# MAIN_BOARD_POWER.net
KiCad netlist of a schematic drawn in Altium Designer
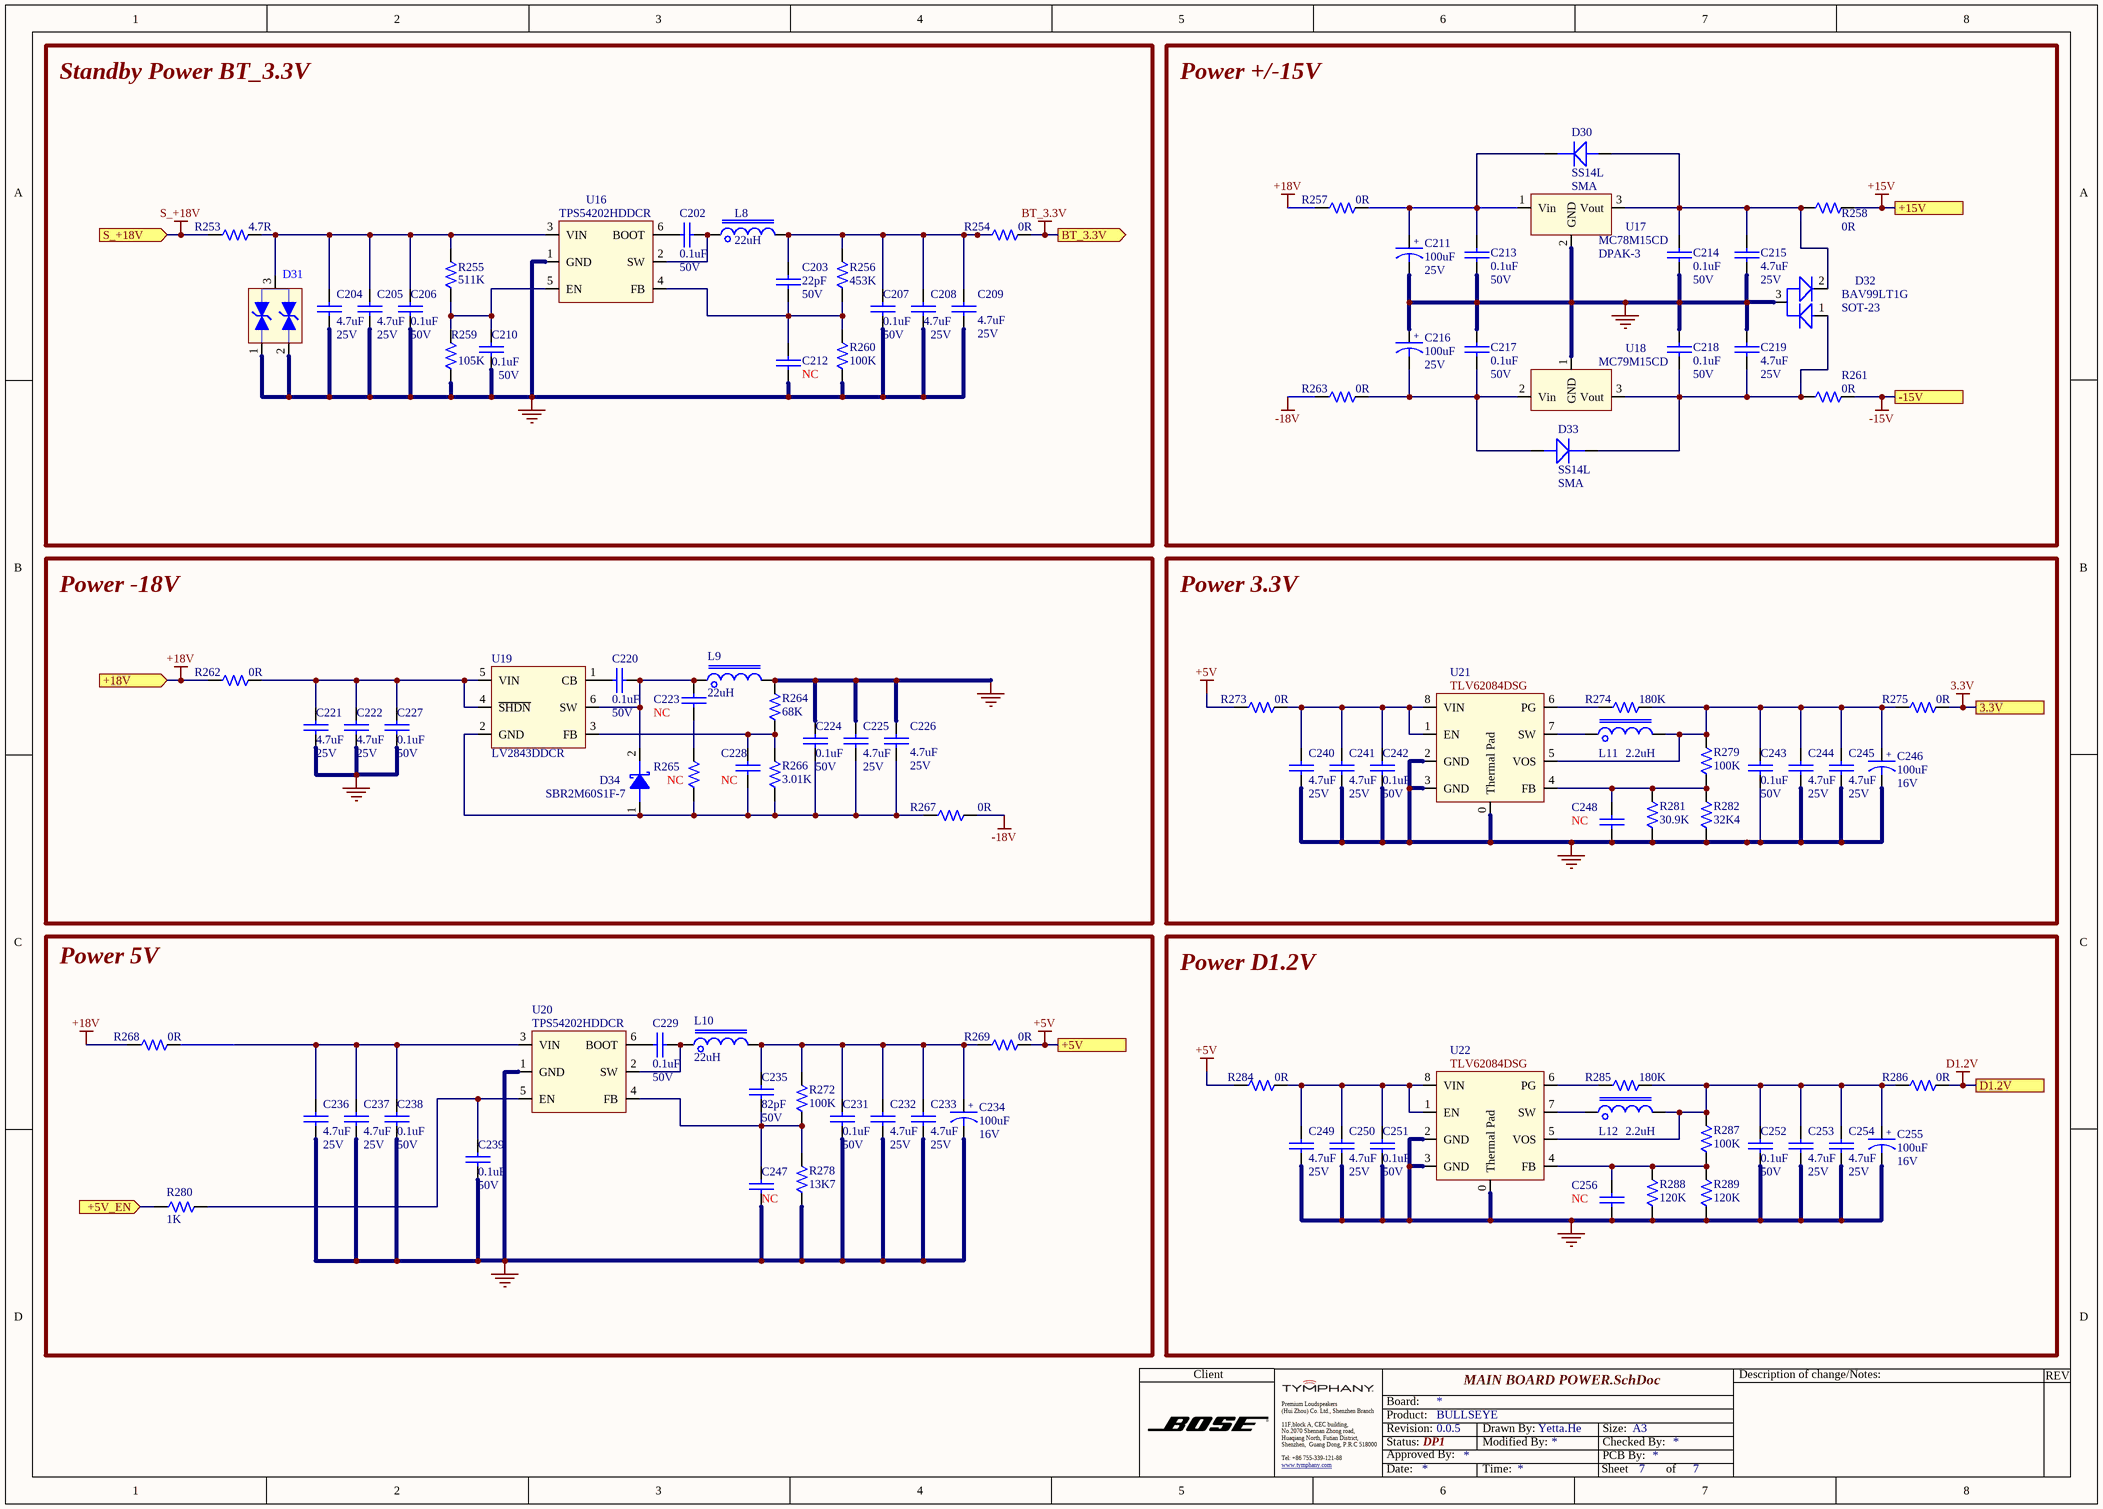
[diagram p0: MAIN BOARD POWER.SchDoc]

(export (version "E")
  (design (tool "Eeschema 10.0.6"))
  (components
    (comp (ref "C202")
      (value "0.1uF")
      (footprint "CAPC0402-RW")
      (description "CAP X7R .10UF 50V +-10% 0402 WALSIN L")
      (fields
        (field (name "TOLERANCE") "10%")
        (field (name "VOLTAGE") "50V")
        (field (name "Comment") "PWL456470-1040")
      )
      (libsource (lib "P-Capacitors") (part "CAP0402 0.1uF 50V 10%"))
    )
    (comp (ref "C203")
      (value "22pF")
      (footprint "CAPC0402-RW")
      (description "CHIP CAP 5% 50V 0402 NPO 22pF")
      (fields
        (field (name "TOLERANCE") "5%")
        (field (name "VOLTAGE") "50V")
        (field (name "Comment") "PWL410370-2200")
      )
      (libsource (lib "P-Capacitors") (part "CAP0402 22pF 50V 5%"))
    )
    (comp (ref "C204")
      (value "4.7uF")
      (footprint "CAPC0603-RW")
      (description "CAP X7R 4.7UF 25V +-10% 0603 WALSIN L")
      (fields (field (name "MFG") "WALSIN") (field (name "TOLERANCE") "10%") (field (name "VOLTAGE") "25V"))
      (libsource (lib "P-Capacitors") (part "CAP0603 4.7uF 25V 10%_X7R_WALSIN"))
    )
    (comp (ref "C205")
      (value "4.7uF")
      (footprint "CAPC0603-RW")
      (description "CAP X7R 4.7UF 25V +-10% 0603 WALSIN L")
      (fields (field (name "MFG") "WALSIN") (field (name "TOLERANCE") "10%") (field (name "VOLTAGE") "25V"))
      (libsource (lib "P-Capacitors") (part "CAP0603 4.7uF 25V 10%_X7R_WALSIN"))
    )
    (comp (ref "C206")
      (value "0.1uF")
      (footprint "CAPC0402-RW")
      (description "CAP X7R .10UF 50V +-10% 0402 WALSIN L")
      (fields
        (field (name "TOLERANCE") "10%")
        (field (name "VOLTAGE") "50V")
        (field (name "Comment") "PWL456470-1040")
      )
      (libsource (lib "P-Capacitors") (part "CAP0402 0.1uF 50V 10%"))
    )
    (comp (ref "C207")
      (value "0.1uF")
      (footprint "CAPC0402-RW")
      (description "CAP X7R .10UF 50V +-10% 0402 WALSIN L")
      (fields
        (field (name "TOLERANCE") "10%")
        (field (name "VOLTAGE") "50V")
        (field (name "Comment") "PWL456470-1040")
      )
      (libsource (lib "P-Capacitors") (part "CAP0402 0.1uF 50V 10%"))
    )
    (comp (ref "C208")
      (value "4.7uF")
      (footprint "CAPC0603-RW")
      (description "CAP X7R 4.7UF 25V +-10% 0603 WALSIN L")
      (fields (field (name "MFG") "WALSIN") (field (name "TOLERANCE") "10%") (field (name "VOLTAGE") "25V"))
      (libsource (lib "P-Capacitors") (part "CAP0603 4.7uF 25V 10%_X7R_WALSIN"))
    )
    (comp (ref "C209")
      (value "4.7uF")
      (footprint "CAPC0603-RW")
      (description "CAP X7R 4.7UF 25V +-10% 0603 WALSIN L")
      (fields (field (name "MFG") "WALSIN") (field (name "TOLERANCE") "10%") (field (name "VOLTAGE") "25V"))
      (libsource (lib "P-Capacitors") (part "CAP0603 4.7uF 25V 10%_X7R_WALSIN"))
    )
    (comp (ref "C210")
      (value "0.1uF")
      (footprint "CAPC0402-RW")
      (description "CAP X7R .10UF 50V +-10% 0402 WALSIN L")
      (fields
        (field (name "TOLERANCE") "10%")
        (field (name "VOLTAGE") "50V")
        (field (name "Comment") "PWL456470-1040")
      )
      (libsource (lib "P-Capacitors") (part "CAP0402 0.1uF 50V 10%"))
    )
    (comp (ref "C211")
      (value "100uF")
      (footprint "CASE - D8")
      (description "E 100UF 25V +-20% 6.3X7. VEJ101M1E K")
      (fields
        (field (name "MFG") "LELON")
        (field (name "MFG PART") "VEJ101M1ETR-0607")
        (field (name "VOLTAGE") "25V")
      )
      (libsource (lib "P-Capacitors") (part "CAP E 100uF 25V 20% SMD_VEJ101M1ETR-0607"))
    )
    (comp (ref "C212")
      (value "NC")
      (footprint "CAPC0603-RW")
      (fields (field (name "Comment") "CAP0603 NC"))
      (libsource (lib "Temporary") (part "CAP0603 NC"))
    )
    (comp (ref "C213")
      (value "0.1uF")
      (footprint "CAPC0402-RW")
      (description "CAP X7R .10UF 50V +-10% 0402 WALSIN L")
      (fields
        (field (name "TOLERANCE") "10%")
        (field (name "VOLTAGE") "50V")
        (field (name "Comment") "PWL456470-1040")
      )
      (libsource (lib "P-Capacitors") (part "CAP0402 0.1uF 50V 10%"))
    )
    (comp (ref "C214")
      (value "0.1uF")
      (footprint "CAPC0402-RW")
      (description "CAP X7R .10UF 50V +-10% 0402 WALSIN L")
      (fields
        (field (name "TOLERANCE") "10%")
        (field (name "VOLTAGE") "50V")
        (field (name "Comment") "PWL456470-1040")
      )
      (libsource (lib "P-Capacitors") (part "CAP0402 0.1uF 50V 10%"))
    )
    (comp (ref "C215")
      (value "4.7uF")
      (footprint "CAPC0603-RW")
      (description "CAP X7R 4.7UF 25V +-10% 0603 WALSIN L")
      (fields (field (name "MFG") "WALSIN") (field (name "TOLERANCE") "10%") (field (name "VOLTAGE") "25V"))
      (libsource (lib "P-Capacitors") (part "CAP0603 4.7uF 25V 10%_X7R_WALSIN"))
    )
    (comp (ref "C216")
      (value "100uF")
      (footprint "CASE - D8")
      (description "E 100UF 25V +-20% 6.3X7. VEJ101M1E K")
      (fields
        (field (name "MFG") "LELON")
        (field (name "MFG PART") "VEJ101M1ETR-0607")
        (field (name "VOLTAGE") "25V")
      )
      (libsource (lib "P-Capacitors") (part "CAP E 100uF 25V 20% SMD_VEJ101M1ETR-0607"))
    )
    (comp (ref "C217")
      (value "0.1uF")
      (footprint "CAPC0402-RW")
      (description "CAP X7R .10UF 50V +-10% 0402 WALSIN L")
      (fields
        (field (name "TOLERANCE") "10%")
        (field (name "VOLTAGE") "50V")
        (field (name "Comment") "PWL456470-1040")
      )
      (libsource (lib "P-Capacitors") (part "CAP0402 0.1uF 50V 10%"))
    )
    (comp (ref "C218")
      (value "0.1uF")
      (footprint "CAPC0402-RW")
      (description "CAP X7R .10UF 50V +-10% 0402 WALSIN L")
      (fields
        (field (name "TOLERANCE") "10%")
        (field (name "VOLTAGE") "50V")
        (field (name "Comment") "PWL456470-1040")
      )
      (libsource (lib "P-Capacitors") (part "CAP0402 0.1uF 50V 10%"))
    )
    (comp (ref "C219")
      (value "4.7uF")
      (footprint "CAPC0603-RW")
      (description "CAP X7R 4.7UF 25V +-10% 0603 WALSIN L")
      (fields (field (name "MFG") "WALSIN") (field (name "TOLERANCE") "10%") (field (name "VOLTAGE") "25V"))
      (libsource (lib "P-Capacitors") (part "CAP0603 4.7uF 25V 10%_X7R_WALSIN"))
    )
    (comp (ref "C220")
      (value "0.1uF")
      (footprint "CAPC0402-RW")
      (description "CAP X7R .10UF 50V +-10% 0402 WALSIN L")
      (fields
        (field (name "TOLERANCE") "10%")
        (field (name "VOLTAGE") "50V")
        (field (name "Comment") "PWL456470-1040")
      )
      (libsource (lib "P-Capacitors") (part "CAP0402 0.1uF 50V 10%"))
    )
    (comp (ref "C221")
      (value "4.7uF")
      (footprint "CAPC0603-RW")
      (description "CAP X7R 4.7UF 25V +-10% 0603 WALSIN L")
      (fields (field (name "MFG") "WALSIN") (field (name "TOLERANCE") "10%") (field (name "VOLTAGE") "25V"))
      (libsource (lib "P-Capacitors") (part "CAP0603 4.7uF 25V 10%_X7R_WALSIN"))
    )
    (comp (ref "C222")
      (value "4.7uF")
      (footprint "CAPC0603-RW")
      (description "CAP X7R 4.7UF 25V +-10% 0603 WALSIN L")
      (fields (field (name "MFG") "WALSIN") (field (name "TOLERANCE") "10%") (field (name "VOLTAGE") "25V"))
      (libsource (lib "P-Capacitors") (part "CAP0603 4.7uF 25V 10%_X7R_WALSIN"))
    )
    (comp (ref "C223")
      (value "NC")
      (footprint "CAPC0603-RW")
      (fields (field (name "Comment") "CAP0603 NC"))
      (libsource (lib "Temporary") (part "CAP0603 NC"))
    )
    (comp (ref "C224")
      (value "0.1uF")
      (footprint "CAPC0402-RW")
      (description "CAP X7R .10UF 50V +-10% 0402 WALSIN L")
      (fields
        (field (name "TOLERANCE") "10%")
        (field (name "VOLTAGE") "50V")
        (field (name "Comment") "PWL456470-1040")
      )
      (libsource (lib "P-Capacitors") (part "CAP0402 0.1uF 50V 10%"))
    )
    (comp (ref "C225")
      (value "4.7uF")
      (footprint "CAPC0603-RW")
      (description "CAP X7R 4.7UF 25V +-10% 0603 WALSIN L")
      (fields (field (name "MFG") "WALSIN") (field (name "TOLERANCE") "10%") (field (name "VOLTAGE") "25V"))
      (libsource (lib "P-Capacitors") (part "CAP0603 4.7uF 25V 10%_X7R_WALSIN"))
    )
    (comp (ref "C226")
      (value "4.7uF")
      (footprint "CAPC0603-RW")
      (description "CAP X7R 4.7UF 25V +-10% 0603 WALSIN L")
      (fields (field (name "MFG") "WALSIN") (field (name "TOLERANCE") "10%") (field (name "VOLTAGE") "25V"))
      (libsource (lib "P-Capacitors") (part "CAP0603 4.7uF 25V 10%_X7R_WALSIN"))
    )
    (comp (ref "C227")
      (value "0.1uF")
      (footprint "CAPC0402-RW")
      (description "CAP X7R .10UF 50V +-10% 0402 WALSIN L")
      (fields
        (field (name "TOLERANCE") "10%")
        (field (name "VOLTAGE") "50V")
        (field (name "Comment") "PWL456470-1040")
      )
      (libsource (lib "P-Capacitors") (part "CAP0402 0.1uF 50V 10%"))
    )
    (comp (ref "C228")
      (value "NC")
      (footprint "CAPC0402-RW")
      (fields (field (name "Comment") "CAP0402 NC"))
      (libsource (lib "Temporary") (part "CAP0402 NC"))
    )
    (comp (ref "C229")
      (value "0.1uF")
      (footprint "CAPC0402-RW")
      (description "CAP X7R .10UF 50V +-10% 0402 WALSIN L")
      (fields
        (field (name "TOLERANCE") "10%")
        (field (name "VOLTAGE") "50V")
        (field (name "Comment") "PWL456470-1040")
      )
      (libsource (lib "P-Capacitors") (part "CAP0402 0.1uF 50V 10%"))
    )
    (comp (ref "C231")
      (value "0.1uF")
      (footprint "CAPC0402-RW")
      (description "CAP X7R .10UF 50V +-10% 0402 WALSIN L")
      (fields
        (field (name "TOLERANCE") "10%")
        (field (name "VOLTAGE") "50V")
        (field (name "Comment") "PWL456470-1040")
      )
      (libsource (lib "P-Capacitors") (part "CAP0402 0.1uF 50V 10%"))
    )
    (comp (ref "C232")
      (value "4.7uF")
      (footprint "CAPC0603-RW")
      (description "CAP X7R 4.7UF 25V +-10% 0603 WALSIN L")
      (fields (field (name "MFG") "WALSIN") (field (name "TOLERANCE") "10%") (field (name "VOLTAGE") "25V"))
      (libsource (lib "P-Capacitors") (part "CAP0603 4.7uF 25V 10%_X7R_WALSIN"))
    )
    (comp (ref "C233")
      (value "4.7uF")
      (footprint "CAPC0603-RW")
      (description "CAP X7R 4.7UF 25V +-10% 0603 WALSIN L")
      (fields (field (name "MFG") "WALSIN") (field (name "TOLERANCE") "10%") (field (name "VOLTAGE") "25V"))
      (libsource (lib "P-Capacitors") (part "CAP0603 4.7uF 25V 10%_X7R_WALSIN"))
    )
    (comp (ref "C234")
      (value "100uF")
      (footprint "CASE - D")
      (description "E 100UF 16V +-20% 6.3*5. VZH101M1C L")
      (fields
        (field (name "MFG") "LELON")
        (field (name "MFG PART") "VZH101M1CTR-0605")
        (field (name "VOLTAGE") "16V")
      )
      (libsource (lib "P-Capacitors") (part "CAP E 100uF 16V 20% SMD-VZH101M1CTR-0605"))
    )
    (comp (ref "C235")
      (value "82pF")
      (footprint "CAPC0603-RW")
      (description "CAP NPO 82PF 50V +-5% 0603 WALSIN L")
      (fields (field (name "MFG") "WALSIN") (field (name "TOLERANCE") "5%") (field (name "VOLTAGE") "50V"))
      (libsource (lib "P-Capacitors") (part "CAP0603 82pF 50V 5%_NPO_WALSIN"))
    )
    (comp (ref "C236")
      (value "4.7uF")
      (footprint "CAPC0603-RW")
      (description "CAP X7R 4.7UF 25V +-10% 0603 WALSIN L")
      (fields (field (name "MFG") "WALSIN") (field (name "TOLERANCE") "10%") (field (name "VOLTAGE") "25V"))
      (libsource (lib "P-Capacitors") (part "CAP0603 4.7uF 25V 10%_X7R_WALSIN"))
    )
    (comp (ref "C237")
      (value "4.7uF")
      (footprint "CAPC0603-RW")
      (description "CAP X7R 4.7UF 25V +-10% 0603 WALSIN L")
      (fields (field (name "MFG") "WALSIN") (field (name "TOLERANCE") "10%") (field (name "VOLTAGE") "25V"))
      (libsource (lib "P-Capacitors") (part "CAP0603 4.7uF 25V 10%_X7R_WALSIN"))
    )
    (comp (ref "C238")
      (value "0.1uF")
      (footprint "CAPC0402-RW")
      (description "CAP X7R .10UF 50V +-10% 0402 WALSIN L")
      (fields
        (field (name "TOLERANCE") "10%")
        (field (name "VOLTAGE") "50V")
        (field (name "Comment") "PWL456470-1040")
      )
      (libsource (lib "P-Capacitors") (part "CAP0402 0.1uF 50V 10%"))
    )
    (comp (ref "C239")
      (value "0.1uF")
      (footprint "CAPC0402-RW")
      (description "CAP X7R .10UF 50V +-10% 0402 WALSIN L")
      (fields
        (field (name "TOLERANCE") "10%")
        (field (name "VOLTAGE") "50V")
        (field (name "Comment") "PWL456470-1040")
      )
      (libsource (lib "P-Capacitors") (part "CAP0402 0.1uF 50V 10%"))
    )
    (comp (ref "C240")
      (value "4.7uF")
      (footprint "CAPC0603-RW")
      (description "CAP X7R 4.7UF 25V +-10% 0603 WALSIN L")
      (fields (field (name "MFG") "WALSIN") (field (name "TOLERANCE") "10%") (field (name "VOLTAGE") "25V"))
      (libsource (lib "P-Capacitors") (part "CAP0603 4.7uF 25V 10%_X7R_WALSIN"))
    )
    (comp (ref "C241")
      (value "4.7uF")
      (footprint "CAPC0603-RW")
      (description "CAP X7R 4.7UF 25V +-10% 0603 WALSIN L")
      (fields (field (name "MFG") "WALSIN") (field (name "TOLERANCE") "10%") (field (name "VOLTAGE") "25V"))
      (libsource (lib "P-Capacitors") (part "CAP0603 4.7uF 25V 10%_X7R_WALSIN"))
    )
    (comp (ref "C242")
      (value "0.1uF")
      (footprint "CAPC0402-RW")
      (description "CAP X7R .10UF 50V +-10% 0402 WALSIN L")
      (fields
        (field (name "TOLERANCE") "10%")
        (field (name "VOLTAGE") "50V")
        (field (name "Comment") "PWL456470-1040")
      )
      (libsource (lib "P-Capacitors") (part "CAP0402 0.1uF 50V 10%"))
    )
    (comp (ref "C243")
      (value "0.1uF")
      (footprint "CAPC0402-RW")
      (description "CAP X7R .10UF 50V +-10% 0402 WALSIN L")
      (fields
        (field (name "TOLERANCE") "10%")
        (field (name "VOLTAGE") "50V")
        (field (name "Comment") "PWL456470-1040")
      )
      (libsource (lib "P-Capacitors") (part "CAP0402 0.1uF 50V 10%"))
    )
    (comp (ref "C244")
      (value "4.7uF")
      (footprint "CAPC0603-RW")
      (description "CAP X7R 4.7UF 25V +-10% 0603 WALSIN L")
      (fields (field (name "MFG") "WALSIN") (field (name "TOLERANCE") "10%") (field (name "VOLTAGE") "25V"))
      (libsource (lib "P-Capacitors") (part "CAP0603 4.7uF 25V 10%_X7R_WALSIN"))
    )
    (comp (ref "C245")
      (value "4.7uF")
      (footprint "CAPC0603-RW")
      (description "CAP X7R 4.7UF 25V +-10% 0603 WALSIN L")
      (fields (field (name "MFG") "WALSIN") (field (name "TOLERANCE") "10%") (field (name "VOLTAGE") "25V"))
      (libsource (lib "P-Capacitors") (part "CAP0603 4.7uF 25V 10%_X7R_WALSIN"))
    )
    (comp (ref "C246")
      (value "100uF")
      (footprint "CASE - D")
      (description "E 100UF 16V +-20% 6.3*5. VZH101M1C L")
      (fields
        (field (name "MFG") "LELON")
        (field (name "MFG PART") "VZH101M1CTR-0605")
        (field (name "VOLTAGE") "16V")
      )
      (libsource (lib "P-Capacitors") (part "CAP E 100uF 16V 20% SMD-VZH101M1CTR-0605"))
    )
    (comp (ref "C247")
      (value "NC")
      (footprint "CAPC0603-RW")
      (fields (field (name "Comment") "CAP0603 NC"))
      (libsource (lib "Temporary") (part "CAP0603 NC"))
    )
    (comp (ref "C248")
      (value "NC")
      (footprint "CAPC0402-RW")
      (fields (field (name "Comment") "CAP0402 NC"))
      (libsource (lib "Temporary") (part "CAP0402 NC"))
    )
    (comp (ref "C249")
      (value "4.7uF")
      (footprint "CAPC0603-RW")
      (description "CAP X7R 4.7UF 25V +-10% 0603 WALSIN L")
      (fields (field (name "MFG") "WALSIN") (field (name "TOLERANCE") "10%") (field (name "VOLTAGE") "25V"))
      (libsource (lib "P-Capacitors") (part "CAP0603 4.7uF 25V 10%_X7R_WALSIN"))
    )
    (comp (ref "C250")
      (value "4.7uF")
      (footprint "CAPC0603-RW")
      (description "CAP X7R 4.7UF 25V +-10% 0603 WALSIN L")
      (fields (field (name "MFG") "WALSIN") (field (name "TOLERANCE") "10%") (field (name "VOLTAGE") "25V"))
      (libsource (lib "P-Capacitors") (part "CAP0603 4.7uF 25V 10%_X7R_WALSIN"))
    )
    (comp (ref "C251")
      (value "0.1uF")
      (footprint "CAPC0402-RW")
      (description "CAP X7R .10UF 50V +-10% 0402 WALSIN L")
      (fields
        (field (name "TOLERANCE") "10%")
        (field (name "VOLTAGE") "50V")
        (field (name "Comment") "PWL456470-1040")
      )
      (libsource (lib "P-Capacitors") (part "CAP0402 0.1uF 50V 10%"))
    )
    (comp (ref "C252")
      (value "0.1uF")
      (footprint "CAPC0402-RW")
      (description "CAP X7R .10UF 50V +-10% 0402 WALSIN L")
      (fields
        (field (name "TOLERANCE") "10%")
        (field (name "VOLTAGE") "50V")
        (field (name "Comment") "PWL456470-1040")
      )
      (libsource (lib "P-Capacitors") (part "CAP0402 0.1uF 50V 10%"))
    )
    (comp (ref "C253")
      (value "4.7uF")
      (footprint "CAPC0603-RW")
      (description "CAP X7R 4.7UF 25V +-10% 0603 WALSIN L")
      (fields (field (name "MFG") "WALSIN") (field (name "TOLERANCE") "10%") (field (name "VOLTAGE") "25V"))
      (libsource (lib "P-Capacitors") (part "CAP0603 4.7uF 25V 10%_X7R_WALSIN"))
    )
    (comp (ref "C254")
      (value "4.7uF")
      (footprint "CAPC0603-RW")
      (description "CAP X7R 4.7UF 25V +-10% 0603 WALSIN L")
      (fields (field (name "MFG") "WALSIN") (field (name "TOLERANCE") "10%") (field (name "VOLTAGE") "25V"))
      (libsource (lib "P-Capacitors") (part "CAP0603 4.7uF 25V 10%_X7R_WALSIN"))
    )
    (comp (ref "C255")
      (value "100uF")
      (footprint "CASE - D")
      (description "E 100UF 16V +-20% 6.3*5. VZH101M1C L")
      (fields
        (field (name "MFG") "LELON")
        (field (name "MFG PART") "VZH101M1CTR-0605")
        (field (name "VOLTAGE") "16V")
      )
      (libsource (lib "P-Capacitors") (part "CAP E 100uF 16V 20% SMD-VZH101M1CTR-0605"))
    )
    (comp (ref "C256")
      (value "NC")
      (footprint "CAPC0402-RW")
      (fields (field (name "Comment") "CAP0402 NC"))
      (libsource (lib "Temporary") (part "CAP0402 NC"))
    )
    (comp (ref "D30")
      (value "RCD100140-0010")
      (footprint "subSMA")
      (description "SMD Schottky Diode Sub SMA 1A 40V SS14L")
      (fields
        (field (name "MFG") "TSC")
        (field (name "VOLTAGE") "40V")
        (field (name "MFG PART") "SS14L")
        (field (name "PACKAGE") "SMA")
      )
      (libsource (lib "R-Semiconductors") (part "SS14L-TSC"))
    )
    (comp (ref "D31")
      (value "RCD100012-0001")
      (footprint "SOT23-132-RW")
      (description "CHIP DIODE ESD CAN01-2BLY SOT23 24V 5.5A")
      (fields (field (name "MFG") "ST") (field (name "MFG PART") "ESDCAN01-2BLY"))
      (libsource (lib "R-Semiconductors") (part "ESDCAN01-2BLY"))
    )
    (comp (ref "D32")
      (value "RCD100099-0010")
      (footprint "SOT23-132-RW")
      (description "SWITC 70V 215MA BAV99LT1G ON SE G")
      (fields
        (field (name "MFG") "ON SEMI")
        (field (name "VOLTAGE") "100V")
        (field (name "PACKAGE") "SOT-23")
        (field (name "MFG PART") "BAV99LT1G")
      )
      (libsource (lib "R-Semiconductors") (part "BAV99LT1G"))
    )
    (comp (ref "D33")
      (value "RCD100140-0010")
      (footprint "subSMA")
      (description "SMD Schottky Diode Sub SMA 1A 40V SS14L")
      (fields
        (field (name "MFG") "TSC")
        (field (name "VOLTAGE") "40V")
        (field (name "MFG PART") "SS14L")
        (field (name "PACKAGE") "SMA")
      )
      (libsource (lib "R-Semiconductors") (part "SS14L-TSC"))
    )
    (comp (ref "D34")
      (value "T572006161416")
      (footprint "SOD-123")
      (description "SWITC 0.7V 2A SBR2M60S1F-7 DIODE L")
      (fields
        (field (name "MFG") "DIODES")
        (field (name "VOLTAGE") "50V")
        (field (name "MFG PART") "SBR2M60S1F-7")
      )
      (libsource (lib "R-Semiconductors") (part "DIO SBR2M60S1F-7"))
    )
    (comp (ref "L8")
      (value "22uH")
      (footprint "IND CKST0505")
      (description "22UH 2 5A 100K 5.7X CENKER CKST050 K")
      (fields (field (name "MFG") "CENKER") (field (name "MFG PART") "CKST0505-22U~{H}M"))
      (libsource (lib "S-Inductor") (part "IND 22uH CKST0505-22UH{backslash}M"))
    )
    (comp (ref "L9")
      (value "22uH")
      (footprint "IND CKST0505")
      (description "22UH 2 5A 100K 5.7X CENKER CKST050 K")
      (fields (field (name "MFG") "CENKER") (field (name "MFG PART") "CKST0505-22U~{H}M"))
      (libsource (lib "S-Inductor") (part "IND 22uH CKST0505-22UH{backslash}M"))
    )
    (comp (ref "L10")
      (value "22uH")
      (footprint "IND CKST0505")
      (description "22UH 2 5A 100K 5.7X CENKER CKST050 K")
      (fields (field (name "MFG") "CENKER") (field (name "MFG PART") "CKST0505-22U~{H}M"))
      (libsource (lib "S-Inductor") (part "IND 22uH CKST0505-22UH{backslash}M"))
    )
    (comp (ref "L11")
      (value "2.2uH")
      (footprint "IND CKCD3D16")
      (description "2.2UH 1.5A 100K SMD CENKER CKCD3D1 K")
      (fields (field (name "MFG") "CENKER") (field (name "MFG PART") "CKCD3D16-2.2U~{H}N"))
      (libsource (lib "S-Inductor") (part "IND 2.2uH CKCD3D16-2.2uH"))
    )
    (comp (ref "L12")
      (value "2.2uH")
      (footprint "IND CKCD3D16")
      (description "2.2UH 1.5A 100K SMD CENKER CKCD3D1 K")
      (fields (field (name "MFG") "CENKER") (field (name "MFG PART") "CKCD3D16-2.2U~{H}N"))
      (libsource (lib "S-Inductor") (part "IND 2.2uH CKCD3D16-2.2uH"))
    )
    (comp (ref "R253")
      (value "4.7R")
      (footprint "0805-RW")
      (description "GP CHIP RES 4.7 OHM 1/8W 1% 0805")
      (fields (field (name "POWER") "1/8W") (field (name "Comment") "QCF081020-4708"))
      (libsource (lib "Q-Resistors") (part "RES0805 1/8W 1% 4.7 OHM"))
    )
    (comp (ref "R254")
      (value "0R")
      (footprint "0805-RW")
      (description "CHIP 0 OHM 0 OHM 0 OHM 0805 WALSI L")
      (fields (field (name "POWER") "1/8W") (field (name "MFG") "WALSIN"))
      (libsource (lib "Q-Resistors") (part "RES0805 1/8W  0 OHM_WALSIN"))
    )
    (comp (ref "R255")
      (value "511K")
      (footprint "0603-RW")
      (description "CHIP RES 511K OHM 1% 1/10W 0603")
      (fields (field (name "Comment") "QCF011030-5113"))
      (libsource (lib "Q-Resistors") (part "RES0603 1/10W 1% 511K OHM"))
    )
    (comp (ref "R256")
      (value "453K")
      (footprint "0402-RW")
      (description "CHIP 453K OHM  100PPM +-1% 0402 WALS")
      (fields (field (name "MFG") "WALSIN (華新)") (field (name "POWER") "1/16W"))
      (libsource (lib "Q-Resistors") (part "RES0402 1/16W 1% 453K OMH_WALSIN"))
    )
    (comp (ref "R257")
      (value "0R")
      (footprint "0805-RW")
      (description "CHIP 0 OHM 0 OHM 0 OHM 0805 WALSI L")
      (fields (field (name "POWER") "1/8W") (field (name "MFG") "WALSIN"))
      (libsource (lib "Q-Resistors") (part "RES0805 1/8W  0 OHM_WALSIN"))
    )
    (comp (ref "R258")
      (value "0R")
      (footprint "0805-RW")
      (description "CHIP 0 OHM 0 OHM 0 OHM 0805 WALSI L")
      (fields (field (name "POWER") "1/8W") (field (name "MFG") "WALSIN"))
      (libsource (lib "Q-Resistors") (part "RES0805 1/8W  0 OHM_WALSIN"))
    )
    (comp (ref "R259")
      (value "105K")
      (footprint "0603-RW")
      (description "CHIP 105K OHM  100PPM +-1% 0603 WALS L")
      (fields (field (name "MFG PART") "WR06X1053FTL") (field (name "MFG") "WALSIN (華新)"))
      (libsource (lib "Q-Resistors") (part "RES0603 1/10W 1% 105K OHM_WALSIN"))
    )
    (comp (ref "R260")
      (value "100K")
      (footprint "0603-RW")
      (description "GP CHIP RES. 100K OHM 1/10W 1% 0603")
      (fields (field (name "Comment") "QCF011030-1003"))
      (libsource (lib "Q-Resistors") (part "RES0603 1/10W 1% 100K OHM"))
    )
    (comp (ref "R261")
      (value "0R")
      (footprint "0805-RW")
      (description "CHIP 0 OHM 0 OHM 0 OHM 0805 WALSI L")
      (fields (field (name "POWER") "1/8W") (field (name "MFG") "WALSIN"))
      (libsource (lib "Q-Resistors") (part "RES0805 1/8W  0 OHM_WALSIN"))
    )
    (comp (ref "R262")
      (value "0R")
      (footprint "0805-RW")
      (description "CHIP 0 OHM 0 OHM 0 OHM 0805 WALSI L")
      (fields (field (name "POWER") "1/8W") (field (name "MFG") "WALSIN"))
      (libsource (lib "Q-Resistors") (part "RES0805 1/8W  0 OHM_WALSIN"))
    )
    (comp (ref "R263")
      (value "0R")
      (footprint "0805-RW")
      (description "CHIP 0 OHM 0 OHM 0 OHM 0805 WALSI L")
      (fields (field (name "POWER") "1/8W") (field (name "MFG") "WALSIN"))
      (libsource (lib "Q-Resistors") (part "RES0805 1/8W  0 OHM_WALSIN"))
    )
    (comp (ref "R264")
      (value "68K")
      (footprint "0603-RW")
      (description "GP CHIP RES. 68K OHM 1/10W 1% 0603")
      (fields (field (name "POWER") "1/10W") (field (name "Comment") "QCF011030-6802"))
      (libsource (lib "Q-Resistors") (part "RES0603 1/10W 1% 68K OHM"))
    )
    (comp (ref "R265")
      (value "NC")
      (footprint "0603-RW")
      (fields (field (name "Comment") "RES0603 NC"))
      (libsource (lib "Temporary") (part "RES0603 NC"))
    )
    (comp (ref "R266")
      (value "3.01K")
      (footprint "0603-RW")
      (description "CHIP RES 3.01K OHM 1% 1/10W  0603")
      (fields (field (name "POWER") "1/10W") (field (name "Comment") "QCF011030-3011"))
      (libsource (lib "Q-Resistors") (part "RES0603 1/10W 1% 3.01K OHM"))
    )
    (comp (ref "R267")
      (value "0R")
      (footprint "0805-RW")
      (description "CHIP 0 OHM 0 OHM 0 OHM 0805 WALSI L")
      (fields (field (name "POWER") "1/8W") (field (name "MFG") "WALSIN"))
      (libsource (lib "Q-Resistors") (part "RES0805 1/8W  0 OHM_WALSIN"))
    )
    (comp (ref "R268")
      (value "0R")
      (footprint "0805-RW")
      (description "CHIP 0 OHM 0 OHM 0 OHM 0805 WALSI L")
      (fields (field (name "POWER") "1/8W") (field (name "MFG") "WALSIN"))
      (libsource (lib "Q-Resistors") (part "RES0805 1/8W  0 OHM_WALSIN"))
    )
    (comp (ref "R269")
      (value "0R")
      (footprint "0805-RW")
      (description "CHIP 0 OHM 0 OHM 0 OHM 0805 WALSI L")
      (fields (field (name "POWER") "1/8W") (field (name "MFG") "WALSIN"))
      (libsource (lib "Q-Resistors") (part "RES0805 1/8W  0 OHM_WALSIN"))
    )
    (comp (ref "R272")
      (value "100K")
      (footprint "0603-RW")
      (description "GP CHIP RES. 100K OHM 1/10W 1% 0603")
      (fields (field (name "Comment") "QCF011030-1003"))
      (libsource (lib "Q-Resistors") (part "RES0603 1/10W 1% 100K OHM"))
    )
    (comp (ref "R273")
      (value "0R")
      (footprint "0805-RW")
      (description "CHIP 0 OHM 0 OHM 0 OHM 0805 WALSI L")
      (fields (field (name "POWER") "1/8W") (field (name "MFG") "WALSIN"))
      (libsource (lib "Q-Resistors") (part "RES0805 1/8W  0 OHM_WALSIN"))
    )
    (comp (ref "R274")
      (value "180K")
      (footprint "0402-RW")
      (description "CHIP RES 100ppm 180K OHM 1% 1/16W 0402")
      (fields (field (name "POWER") "1/16W") (field (name "Comment") "QCF161240-1803"))
      (libsource (lib "Q-Resistors") (part "RES0402 1/16W 1% 180K OHM 100PPM"))
    )
    (comp (ref "R275")
      (value "0R")
      (footprint "0805-RW")
      (description "CHIP 0 OHM 0 OHM 0 OHM 0805 WALSI L")
      (fields (field (name "POWER") "1/8W") (field (name "MFG") "WALSIN"))
      (libsource (lib "Q-Resistors") (part "RES0805 1/8W  0 OHM_WALSIN"))
    )
    (comp (ref "R278")
      (value "13K7")
      (footprint "0603-RW")
      (description "CHIP 13.7K OHM 100PPM +-1% 0603 WALS L")
      (fields (field (name "MFG") "WALSIN (華新)") (field (name "Comment") "T502137202399"))
      (libsource (lib "Q-Resistors") (part "RES0603 1/10W 1% 13.7K OHM_WALSIN"))
    )
    (comp (ref "R279")
      (value "100K")
      (footprint "0603-RW")
      (description "GP CHIP RES. 100K OHM 1/10W 1% 0603")
      (fields (field (name "POWER") "1/10W") (field (name "Comment") "QCF011030-1003"))
      (libsource (lib "Q-Resistors") (part "RES0603 1/10W 1% 100K OHM"))
    )
    (comp (ref "R280")
      (value "1K")
      (footprint "0603-RW")
      (description "GP CHIP RES. 1K OHM 1/10W 1% 0603")
      (fields (field (name "POWER") "1/10W") (field (name "Comment") "QCF011030-1001"))
      (libsource (lib "Q-Resistors") (part "RES0603 1/10W 1% 1K OHM"))
    )
    (comp (ref "R281")
      (value "30.9K")
      (footprint "0603-RW")
      (description "CHIP RES. 30.9K OHM 1/10W 1% 0603")
      (fields (field (name "POWER") "1/10W") (field (name "Comment") "QCF011030-3092"))
      (libsource (lib "Q-Resistors") (part "RES0603 1/10W 1% 30.9K OHM"))
    )
    (comp (ref "R282")
      (value "32K4")
      (footprint "0402-RW")
      (description "CHIP RES 32.4K OHM 1% 1/16W 0402")
      (fields (field (name "POWER") "1/16W") (field (name "Comment") "QCF161240-3242"))
      (libsource (lib "Q-Resistors") (part "RES0402 1/16W 1% 32.4K OHM"))
    )
    (comp (ref "R284")
      (value "0R")
      (footprint "0805-RW")
      (description "CHIP 0 OHM 0 OHM 0 OHM 0805 WALSI L")
      (fields (field (name "POWER") "1/8W") (field (name "MFG") "WALSIN"))
      (libsource (lib "Q-Resistors") (part "RES0805 1/8W  0 OHM_WALSIN"))
    )
    (comp (ref "R285")
      (value "180K")
      (footprint "0402-RW")
      (description "CHIP RES 100ppm 180K OHM 1% 1/16W 0402")
      (fields (field (name "POWER") "1/16W") (field (name "Comment") "QCF161240-1803"))
      (libsource (lib "Q-Resistors") (part "RES0402 1/16W 1% 180K OHM 100PPM"))
    )
    (comp (ref "R286")
      (value "0R")
      (footprint "0805-RW")
      (description "CHIP 0 OHM 0 OHM 0 OHM 0805 WALSI L")
      (fields (field (name "POWER") "1/8W") (field (name "MFG") "WALSIN"))
      (libsource (lib "Q-Resistors") (part "RES0805 1/8W  0 OHM_WALSIN"))
    )
    (comp (ref "R287")
      (value "100K")
      (footprint "0603-RW")
      (description "GP CHIP RES. 100K OHM 1/10W 1% 0603")
      (fields (field (name "POWER") "1/10W") (field (name "Comment") "QCF011030-1003"))
      (libsource (lib "Q-Resistors") (part "RES0603 1/10W 1% 100K OHM"))
    )
    (comp (ref "R288")
      (value "120K")
      (footprint "0603-RW")
      (description "CHIP RES 120K OHM 1% 1/10W 0603")
      (fields (field (name "POWER") "1/10W") (field (name "Comment") "QCF011030-1203"))
      (libsource (lib "Q-Resistors") (part "RES0603 1/10W 1% 120K OHM"))
    )
    (comp (ref "R289")
      (value "120K")
      (footprint "0603-RW")
      (description "CHIP RES 120K OHM 1% 1/10W 0603")
      (fields (field (name "POWER") "1/10W") (field (name "Comment") "QCF011030-1203"))
      (libsource (lib "Q-Resistors") (part "RES0603 1/10W 1% 120K OHM"))
    )
    (comp (ref "U16")
      (value "T611700039022")
      (footprint "SOT23-6 P.95")
      (description "DC DC CVT TPS54202HDD SOT-23(6) TI K")
      (fields (field (name "MFG") "TI") (field (name "MFG PART") "TPS54202HDDCR"))
      (libsource (lib "R-Semiconductors") (part "TPS54202"))
    )
    (comp (ref "U17")
      (value "T610600097341")
      (footprint "DPAK-3")
      (description "REG MC78M15CD TO-252 ON K")
      (fields
        (field (name "MFG") "ON")
        (field (name "VOLTAGE") "15V")
        (field (name "MFG PART") "MC78M15CD")
        (field (name "PACKAGE") "DPAK-3")
      )
      (libsource (lib "R-Semiconductors") (part "MC78M15CD"))
    )
    (comp (ref "U18")
      (value "T610600097241")
      (footprint "DPAK-3")
      (description "REG MC79M15CD TO-252 ON K")
      (fields (field (name "MFG") "ON SEMICONDUCTOR") (field (name "MFG PART") "MC79M15CD"))
      (libsource (lib "R-Semiconductors") (part "MC79M15CD"))
    )
    (comp (ref "U19")
      (value "RCI002843-0001")
      (footprint "DBV(R-PDSO-G6)")
      (description "REG LV2843 TSOT23-6 TI G")
      (fields (field (name "MFG") "TI") (field (name "MFG PART") "LV2843DDCR"))
      (libsource (lib "R-Semiconductors") (part "LV2843"))
    )
    (comp (ref "U20")
      (value "T611700039022")
      (footprint "SOT23-6 P.95")
      (description "DC DC CVT TPS54202HDD SOT-23(6) TI K")
      (fields (field (name "MFG") "TI") (field (name "MFG PART") "TPS54202HDDCR"))
      (libsource (lib "R-Semiconductors") (part "TPS54202"))
    )
    (comp (ref "U21")
      (value "T611700037422")
      (footprint "DSG(S-PWSON-N8)")
      (description "DC DC CVT TLV62084DSG WSON8 TI G")
      (fields (field (name "MFG") "TI") (field (name "MFG PART") "TLV62084DSG"))
      (libsource (lib "R-Semiconductors") (part "TLV62084DSG"))
    )
    (comp (ref "U22")
      (value "T611700037422")
      (footprint "DSG(S-PWSON-N8)")
      (description "DC DC CVT TLV62084DSG WSON8 TI G")
      (fields (field (name "MFG") "TI") (field (name "MFG PART") "TLV62084DSG"))
      (libsource (lib "R-Semiconductors") (part "TLV62084DSG"))
    )
  )
  (nets
    (net (code "1") (name "+5V") (class "Default")
      (node (ref "R269") (pin "2") (pinfunction "2_2") (pintype "passive"))
      (node (ref "R273") (pin "1") (pinfunction "1_1") (pintype "passive"))
      (node (ref "R284") (pin "1") (pinfunction "1_1") (pintype "passive"))
    )
    (net (code "2") (name "+15V") (class "Default")
      (node (ref "R258") (pin "2") (pinfunction "2_2") (pintype "passive"))
    )
    (net (code "3") (name "+18V") (class "Default")
      (node (ref "R257") (pin "1") (pinfunction "1_1") (pintype "passive"))
      (node (ref "R262") (pin "1") (pinfunction "1_1") (pintype "passive"))
      (node (ref "R268") (pin "1") (pinfunction "1_1") (pintype "passive"))
    )
    (net (code "4") (name "-15V") (class "Default")
      (node (ref "R261") (pin "2") (pinfunction "2_2") (pintype "passive"))
    )
    (net (code "5") (name "-18V") (class "Default")
      (node (ref "R263") (pin "1") (pinfunction "1_1") (pintype "passive"))
      (node (ref "R267") (pin "2") (pinfunction "2_2") (pintype "passive"))
    )
    (net (code "6") (name "/+5V_EN") (class "Default")
      (node (ref "R280") (pin "1") (pinfunction "1_1") (pintype "passive"))
    )
    (net (code "7") (name "3.3V") (class "Default")
      (node (ref "R275") (pin "2") (pinfunction "2_2") (pintype "passive"))
    )
    (net (code "8") (name "BT_3.3V") (class "Default")
      (node (ref "R254") (pin "2") (pinfunction "2_2") (pintype "passive"))
    )
    (net (code "9") (name "D1.2V") (class "Default")
      (node (ref "R286") (pin "2") (pinfunction "2_2") (pintype "passive"))
    )
    (net (code "10") (name "GND") (class "Default")
      (node (ref "C204") (pin "2") (pinfunction "2_2") (pintype "passive"))
      (node (ref "C205") (pin "2") (pinfunction "2_2") (pintype "passive"))
      (node (ref "C206") (pin "2") (pinfunction "2_2") (pintype "passive"))
      (node (ref "C207") (pin "2") (pinfunction "2_2") (pintype "passive"))
      (node (ref "C208") (pin "2") (pinfunction "2_2") (pintype "passive"))
      (node (ref "C209") (pin "2") (pinfunction "2_2") (pintype "passive"))
      (node (ref "C210") (pin "2") (pinfunction "2_2") (pintype "passive"))
      (node (ref "C211") (pin "2") (pinfunction "2_2") (pintype "passive"))
      (node (ref "C212") (pin "2") (pinfunction "2_2") (pintype "passive"))
      (node (ref "C213") (pin "2") (pinfunction "2_2") (pintype "passive"))
      (node (ref "C214") (pin "2") (pinfunction "2_2") (pintype "passive"))
      (node (ref "C215") (pin "2") (pinfunction "2_2") (pintype "passive"))
      (node (ref "C216") (pin "1") (pinfunction "1_1") (pintype "passive"))
      (node (ref "C217") (pin "1") (pinfunction "1_1") (pintype "passive"))
      (node (ref "C218") (pin "1") (pinfunction "1_1") (pintype "passive"))
      (node (ref "C219") (pin "1") (pinfunction "1_1") (pintype "passive"))
      (node (ref "C221") (pin "2") (pinfunction "2_2") (pintype "passive"))
      (node (ref "C222") (pin "2") (pinfunction "2_2") (pintype "passive"))
      (node (ref "C224") (pin "1") (pinfunction "1_1") (pintype "passive"))
      (node (ref "C225") (pin "1") (pinfunction "1_1") (pintype "passive"))
      (node (ref "C226") (pin "1") (pinfunction "1_1") (pintype "passive"))
      (node (ref "C227") (pin "2") (pinfunction "2_2") (pintype "passive"))
      (node (ref "C231") (pin "2") (pinfunction "2_2") (pintype "passive"))
      (node (ref "C232") (pin "2") (pinfunction "2_2") (pintype "passive"))
      (node (ref "C233") (pin "2") (pinfunction "2_2") (pintype "passive"))
      (node (ref "C234") (pin "2") (pinfunction "2_2") (pintype "passive"))
      (node (ref "C236") (pin "2") (pinfunction "2_2") (pintype "passive"))
      (node (ref "C237") (pin "2") (pinfunction "2_2") (pintype "passive"))
      (node (ref "C238") (pin "2") (pinfunction "2_2") (pintype "passive"))
      (node (ref "C239") (pin "2") (pinfunction "2_2") (pintype "passive"))
      (node (ref "C240") (pin "2") (pinfunction "2_2") (pintype "passive"))
      (node (ref "C241") (pin "2") (pinfunction "2_2") (pintype "passive"))
      (node (ref "C242") (pin "2") (pinfunction "2_2") (pintype "passive"))
      (node (ref "C243") (pin "2") (pinfunction "2_2") (pintype "passive"))
      (node (ref "C244") (pin "2") (pinfunction "2_2") (pintype "passive"))
      (node (ref "C245") (pin "2") (pinfunction "2_2") (pintype "passive"))
      (node (ref "C246") (pin "2") (pinfunction "2_2") (pintype "passive"))
      (node (ref "C247") (pin "2") (pinfunction "2_2") (pintype "passive"))
      (node (ref "C248") (pin "2") (pinfunction "2_2") (pintype "passive"))
      (node (ref "C249") (pin "2") (pinfunction "2_2") (pintype "passive"))
      (node (ref "C250") (pin "2") (pinfunction "2_2") (pintype "passive"))
      (node (ref "C251") (pin "2") (pinfunction "2_2") (pintype "passive"))
      (node (ref "C252") (pin "2") (pinfunction "2_2") (pintype "passive"))
      (node (ref "C253") (pin "2") (pinfunction "2_2") (pintype "passive"))
      (node (ref "C254") (pin "2") (pinfunction "2_2") (pintype "passive"))
      (node (ref "C255") (pin "2") (pinfunction "2_2") (pintype "passive"))
      (node (ref "C256") (pin "2") (pinfunction "2_2") (pintype "passive"))
      (node (ref "D31") (pin "1") (pinfunction "A_1") (pintype "passive"))
      (node (ref "D31") (pin "2") (pinfunction "A_2") (pintype "passive"))
      (node (ref "D32") (pin "3") (pinfunction "K_3") (pintype "passive"))
      (node (ref "L9") (pin "2") (pinfunction "2_2") (pintype "passive"))
      (node (ref "R259") (pin "1") (pinfunction "1_1") (pintype "passive"))
      (node (ref "R260") (pin "1") (pinfunction "1_1") (pintype "passive"))
      (node (ref "R264") (pin "2") (pinfunction "2_2") (pintype "passive"))
      (node (ref "R278") (pin "1") (pinfunction "1_1") (pintype "passive"))
      (node (ref "R281") (pin "1") (pinfunction "1_1") (pintype "passive"))
      (node (ref "R282") (pin "1") (pinfunction "1_1") (pintype "passive"))
      (node (ref "R288") (pin "1") (pinfunction "1_1") (pintype "passive"))
      (node (ref "R289") (pin "1") (pinfunction "1_1") (pintype "passive"))
      (node (ref "U16") (pin "1") (pinfunction "GND_1") (pintype "passive"))
      (node (ref "U17") (pin "2") (pinfunction "GND_2") (pintype "passive"))
      (node (ref "U18") (pin "1") (pinfunction "GND_1") (pintype "passive"))
      (node (ref "U20") (pin "1") (pinfunction "GND_1") (pintype "passive"))
      (node (ref "U21") (pin "0") (pinfunction "Thermal_Pad_0") (pintype "passive"))
      (node (ref "U21") (pin "2") (pinfunction "GND_2") (pintype "passive"))
      (node (ref "U21") (pin "3") (pinfunction "GND_3") (pintype "passive"))
      (node (ref "U22") (pin "0") (pinfunction "Thermal_Pad_0") (pintype "passive"))
      (node (ref "U22") (pin "2") (pinfunction "GND_2") (pintype "passive"))
      (node (ref "U22") (pin "3") (pinfunction "GND_3") (pintype "passive"))
    )
    (net (code "11") (name "Net-(C203-Pad1)") (class "Default")
      (node (ref "C203") (pin "1") (pinfunction "1_1") (pintype "passive"))
      (node (ref "C207") (pin "1") (pinfunction "1_1") (pintype "passive"))
      (node (ref "C208") (pin "1") (pinfunction "1_1") (pintype "passive"))
      (node (ref "C209") (pin "1") (pinfunction "1_1") (pintype "passive"))
      (node (ref "L8") (pin "2") (pinfunction "2_2") (pintype "passive"))
      (node (ref "R254") (pin "1") (pinfunction "1_1") (pintype "passive"))
      (node (ref "R256") (pin "2") (pinfunction "2_2") (pintype "passive"))
    )
    (net (code "12") (name "Net-(C223-Pad2)") (class "Default")
      (node (ref "C223") (pin "2") (pinfunction "2_2") (pintype "passive"))
      (node (ref "R265") (pin "2") (pinfunction "2_2") (pintype "passive"))
    )
    (net (code "13") (name "Net-(C231-Pad1)") (class "Default")
      (node (ref "C231") (pin "1") (pinfunction "1_1") (pintype "passive"))
      (node (ref "C232") (pin "1") (pinfunction "1_1") (pintype "passive"))
      (node (ref "C233") (pin "1") (pinfunction "1_1") (pintype "passive"))
      (node (ref "C234") (pin "1") (pinfunction "1_1") (pintype "passive"))
      (node (ref "C235") (pin "1") (pinfunction "1_1") (pintype "passive"))
      (node (ref "L10") (pin "2") (pinfunction "2_2") (pintype "passive"))
      (node (ref "R269") (pin "1") (pinfunction "1_1") (pintype "passive"))
      (node (ref "R272") (pin "2") (pinfunction "2_2") (pintype "passive"))
    )
    (net (code "14") (name "Net-(D30-A)") (class "Default")
      (node (ref "C214") (pin "1") (pinfunction "1_1") (pintype "passive"))
      (node (ref "C215") (pin "1") (pinfunction "1_1") (pintype "passive"))
      (node (ref "D30") (pin "1") (pinfunction "A_1") (pintype "passive"))
      (node (ref "D32") (pin "2") (pinfunction "A_2") (pintype "passive"))
      (node (ref "R258") (pin "1") (pinfunction "1_1") (pintype "passive"))
      (node (ref "U17") (pin "3") (pinfunction "Vout_3") (pintype "passive"))
    )
    (net (code "15") (name "Net-(D30-K)") (class "Default")
      (node (ref "C211") (pin "1") (pinfunction "1_1") (pintype "passive"))
      (node (ref "C213") (pin "1") (pinfunction "1_1") (pintype "passive"))
      (node (ref "D30") (pin "2") (pinfunction "K_2") (pintype "passive"))
      (node (ref "R257") (pin "2") (pinfunction "2_2") (pintype "passive"))
      (node (ref "U17") (pin "1") (pinfunction "Vin_1") (pintype "passive"))
    )
    (net (code "16") (name "Net-(D31-K)") (class "Default")
      (node (ref "C204") (pin "1") (pinfunction "1_1") (pintype "passive"))
      (node (ref "C205") (pin "1") (pinfunction "1_1") (pintype "passive"))
      (node (ref "C206") (pin "1") (pinfunction "1_1") (pintype "passive"))
      (node (ref "D31") (pin "3") (pinfunction "K_3") (pintype "passive"))
      (node (ref "R253") (pin "2") (pinfunction "2_2") (pintype "passive"))
      (node (ref "R255") (pin "2") (pinfunction "2_2") (pintype "passive"))
      (node (ref "U16") (pin "3") (pinfunction "VIN_3") (pintype "passive"))
    )
    (net (code "17") (name "Net-(D33-A)") (class "Default")
      (node (ref "C216") (pin "2") (pinfunction "2_2") (pintype "passive"))
      (node (ref "C217") (pin "2") (pinfunction "2_2") (pintype "passive"))
      (node (ref "D33") (pin "1") (pinfunction "A_1") (pintype "passive"))
      (node (ref "R263") (pin "2") (pinfunction "2_2") (pintype "passive"))
      (node (ref "U18") (pin "2") (pinfunction "Vin_2") (pintype "passive"))
    )
    (net (code "18") (name "Net-(D33-K)") (class "Default")
      (node (ref "C218") (pin "2") (pinfunction "2_2") (pintype "passive"))
      (node (ref "C219") (pin "2") (pinfunction "2_2") (pintype "passive"))
      (node (ref "D32") (pin "1") (pinfunction "A_1") (pintype "passive"))
      (node (ref "D33") (pin "2") (pinfunction "K_2") (pintype "passive"))
      (node (ref "R261") (pin "1") (pinfunction "1_1") (pintype "passive"))
      (node (ref "U18") (pin "3") (pinfunction "Vout_3") (pintype "passive"))
    )
    (net (code "19") (name "Net-(D34-A)") (class "Default")
      (node (ref "C224") (pin "2") (pinfunction "2_2") (pintype "passive"))
      (node (ref "C225") (pin "2") (pinfunction "2_2") (pintype "passive"))
      (node (ref "C226") (pin "2") (pinfunction "2_2") (pintype "passive"))
      (node (ref "C228") (pin "2") (pinfunction "2_2") (pintype "passive"))
      (node (ref "D34") (pin "1") (pinfunction "A_1") (pintype "passive"))
      (node (ref "R265") (pin "1") (pinfunction "1_1") (pintype "passive"))
      (node (ref "R266") (pin "1") (pinfunction "1_1") (pintype "passive"))
      (node (ref "R267") (pin "1") (pinfunction "1_1") (pintype "passive"))
      (node (ref "U19") (pin "2") (pinfunction "GND_2") (pintype "passive"))
    )
    (net (code "20") (name "Net-(D34-K)") (class "Default")
      (node (ref "C220") (pin "2") (pinfunction "2_2") (pintype "passive"))
      (node (ref "C223") (pin "1") (pinfunction "1_1") (pintype "passive"))
      (node (ref "D34") (pin "2") (pinfunction "K_2") (pintype "passive"))
      (node (ref "L9") (pin "1") (pinfunction "1_1") (pintype "passive"))
      (node (ref "U19") (pin "6") (pinfunction "SW_6") (pintype "passive"))
    )
    (net (code "21") (name "Net-(U16-BOOT)") (class "Default")
      (node (ref "C202") (pin "1") (pinfunction "1_1") (pintype "passive"))
      (node (ref "U16") (pin "6") (pinfunction "BOOT_6") (pintype "passive"))
    )
    (net (code "22") (name "Net-(U16-EN)") (class "Default")
      (node (ref "C210") (pin "1") (pinfunction "1_1") (pintype "passive"))
      (node (ref "R255") (pin "1") (pinfunction "1_1") (pintype "passive"))
      (node (ref "R259") (pin "2") (pinfunction "2_2") (pintype "passive"))
      (node (ref "U16") (pin "5") (pinfunction "EN_5") (pintype "passive"))
    )
    (net (code "23") (name "Net-(U16-FB)") (class "Default")
      (node (ref "C203") (pin "2") (pinfunction "2_2") (pintype "passive"))
      (node (ref "C212") (pin "1") (pinfunction "1_1") (pintype "passive"))
      (node (ref "R256") (pin "1") (pinfunction "1_1") (pintype "passive"))
      (node (ref "R260") (pin "2") (pinfunction "2_2") (pintype "passive"))
      (node (ref "U16") (pin "4") (pinfunction "FB_4") (pintype "passive"))
    )
    (net (code "24") (name "Net-(U16-SW)") (class "Default")
      (node (ref "C202") (pin "2") (pinfunction "2_2") (pintype "passive"))
      (node (ref "L8") (pin "1") (pinfunction "1_1") (pintype "passive"))
      (node (ref "U16") (pin "2") (pinfunction "SW_2") (pintype "passive"))
    )
    (net (code "25") (name "Net-(U19-CB)") (class "Default")
      (node (ref "C220") (pin "1") (pinfunction "1_1") (pintype "passive"))
      (node (ref "U19") (pin "1") (pinfunction "CB_1") (pintype "passive"))
    )
    (net (code "26") (name "Net-(U19-FB)") (class "Default")
      (node (ref "C228") (pin "1") (pinfunction "1_1") (pintype "passive"))
      (node (ref "R264") (pin "1") (pinfunction "1_1") (pintype "passive"))
      (node (ref "R266") (pin "2") (pinfunction "2_2") (pintype "passive"))
      (node (ref "U19") (pin "3") (pinfunction "FB_3") (pintype "passive"))
    )
    (net (code "27") (name "Net-(U19-VIN)") (class "Default")
      (node (ref "C221") (pin "1") (pinfunction "1_1") (pintype "passive"))
      (node (ref "C222") (pin "1") (pinfunction "1_1") (pintype "passive"))
      (node (ref "C227") (pin "1") (pinfunction "1_1") (pintype "passive"))
      (node (ref "R262") (pin "2") (pinfunction "2_2") (pintype "passive"))
      (node (ref "U19") (pin "4") (pinfunction "~{SHDN}_4") (pintype "passive"))
      (node (ref "U19") (pin "5") (pinfunction "VIN_5") (pintype "passive"))
    )
    (net (code "28") (name "Net-(U20-BOOT)") (class "Default")
      (node (ref "C229") (pin "1") (pinfunction "1_1") (pintype "passive"))
      (node (ref "U20") (pin "6") (pinfunction "BOOT_6") (pintype "passive"))
    )
    (net (code "29") (name "Net-(U20-EN)") (class "Default")
      (node (ref "C239") (pin "1") (pinfunction "1_1") (pintype "passive"))
      (node (ref "R280") (pin "2") (pinfunction "2_2") (pintype "passive"))
      (node (ref "U20") (pin "5") (pinfunction "EN_5") (pintype "passive"))
    )
    (net (code "30") (name "Net-(U20-FB)") (class "Default")
      (node (ref "C235") (pin "2") (pinfunction "2_2") (pintype "passive"))
      (node (ref "C247") (pin "1") (pinfunction "1_1") (pintype "passive"))
      (node (ref "R272") (pin "1") (pinfunction "1_1") (pintype "passive"))
      (node (ref "R278") (pin "2") (pinfunction "2_2") (pintype "passive"))
      (node (ref "U20") (pin "4") (pinfunction "FB_4") (pintype "passive"))
    )
    (net (code "31") (name "Net-(U20-SW)") (class "Default")
      (node (ref "C229") (pin "2") (pinfunction "2_2") (pintype "passive"))
      (node (ref "L10") (pin "1") (pinfunction "1_1") (pintype "passive"))
      (node (ref "U20") (pin "2") (pinfunction "SW_2") (pintype "passive"))
    )
    (net (code "32") (name "Net-(U20-VIN)") (class "Default")
      (node (ref "C236") (pin "1") (pinfunction "1_1") (pintype "passive"))
      (node (ref "C237") (pin "1") (pinfunction "1_1") (pintype "passive"))
      (node (ref "C238") (pin "1") (pinfunction "1_1") (pintype "passive"))
      (node (ref "R268") (pin "2") (pinfunction "2_2") (pintype "passive"))
      (node (ref "U20") (pin "3") (pinfunction "VIN_3") (pintype "passive"))
    )
    (net (code "33") (name "Net-(U21-EN)") (class "Default")
      (node (ref "C240") (pin "1") (pinfunction "1_1") (pintype "passive"))
      (node (ref "C241") (pin "1") (pinfunction "1_1") (pintype "passive"))
      (node (ref "C242") (pin "1") (pinfunction "1_1") (pintype "passive"))
      (node (ref "R273") (pin "2") (pinfunction "2_2") (pintype "passive"))
      (node (ref "U21") (pin "1") (pinfunction "EN_1") (pintype "passive"))
      (node (ref "U21") (pin "8") (pinfunction "VIN_8") (pintype "passive"))
    )
    (net (code "34") (name "Net-(U21-FB)") (class "Default")
      (node (ref "C248") (pin "1") (pinfunction "1_1") (pintype "passive"))
      (node (ref "R279") (pin "1") (pinfunction "1_1") (pintype "passive"))
      (node (ref "R281") (pin "2") (pinfunction "2_2") (pintype "passive"))
      (node (ref "R282") (pin "2") (pinfunction "2_2") (pintype "passive"))
      (node (ref "U21") (pin "4") (pinfunction "FB_4") (pintype "passive"))
    )
    (net (code "35") (name "Net-(U21-PG)") (class "Default")
      (node (ref "R274") (pin "1") (pinfunction "1_1") (pintype "passive"))
      (node (ref "U21") (pin "6") (pinfunction "PG_6") (pintype "passive"))
    )
    (net (code "36") (name "Net-(U21-SW)") (class "Default")
      (node (ref "L11") (pin "1") (pinfunction "1_1") (pintype "passive"))
      (node (ref "U21") (pin "7") (pinfunction "SW_7") (pintype "passive"))
    )
    (net (code "37") (name "Net-(U21-VOS)") (class "Default")
      (node (ref "C243") (pin "1") (pinfunction "1_1") (pintype "passive"))
      (node (ref "C244") (pin "1") (pinfunction "1_1") (pintype "passive"))
      (node (ref "C245") (pin "1") (pinfunction "1_1") (pintype "passive"))
      (node (ref "C246") (pin "1") (pinfunction "1_1") (pintype "passive"))
      (node (ref "L11") (pin "2") (pinfunction "2_2") (pintype "passive"))
      (node (ref "R274") (pin "2") (pinfunction "2_2") (pintype "passive"))
      (node (ref "R275") (pin "1") (pinfunction "1_1") (pintype "passive"))
      (node (ref "R279") (pin "2") (pinfunction "2_2") (pintype "passive"))
      (node (ref "U21") (pin "5") (pinfunction "VOS_5") (pintype "passive"))
    )
    (net (code "38") (name "Net-(U22-EN)") (class "Default")
      (node (ref "C249") (pin "1") (pinfunction "1_1") (pintype "passive"))
      (node (ref "C250") (pin "1") (pinfunction "1_1") (pintype "passive"))
      (node (ref "C251") (pin "1") (pinfunction "1_1") (pintype "passive"))
      (node (ref "R284") (pin "2") (pinfunction "2_2") (pintype "passive"))
      (node (ref "U22") (pin "1") (pinfunction "EN_1") (pintype "passive"))
      (node (ref "U22") (pin "8") (pinfunction "VIN_8") (pintype "passive"))
    )
    (net (code "39") (name "Net-(U22-FB)") (class "Default")
      (node (ref "C256") (pin "1") (pinfunction "1_1") (pintype "passive"))
      (node (ref "R287") (pin "1") (pinfunction "1_1") (pintype "passive"))
      (node (ref "R288") (pin "2") (pinfunction "2_2") (pintype "passive"))
      (node (ref "R289") (pin "2") (pinfunction "2_2") (pintype "passive"))
      (node (ref "U22") (pin "4") (pinfunction "FB_4") (pintype "passive"))
    )
    (net (code "40") (name "Net-(U22-PG)") (class "Default")
      (node (ref "R285") (pin "1") (pinfunction "1_1") (pintype "passive"))
      (node (ref "U22") (pin "6") (pinfunction "PG_6") (pintype "passive"))
    )
    (net (code "41") (name "Net-(U22-SW)") (class "Default")
      (node (ref "L12") (pin "1") (pinfunction "1_1") (pintype "passive"))
      (node (ref "U22") (pin "7") (pinfunction "SW_7") (pintype "passive"))
    )
    (net (code "42") (name "Net-(U22-VOS)") (class "Default")
      (node (ref "C252") (pin "1") (pinfunction "1_1") (pintype "passive"))
      (node (ref "C253") (pin "1") (pinfunction "1_1") (pintype "passive"))
      (node (ref "C254") (pin "1") (pinfunction "1_1") (pintype "passive"))
      (node (ref "C255") (pin "1") (pinfunction "1_1") (pintype "passive"))
      (node (ref "L12") (pin "2") (pinfunction "2_2") (pintype "passive"))
      (node (ref "R285") (pin "2") (pinfunction "2_2") (pintype "passive"))
      (node (ref "R286") (pin "1") (pinfunction "1_1") (pintype "passive"))
      (node (ref "R287") (pin "2") (pinfunction "2_2") (pintype "passive"))
      (node (ref "U22") (pin "5") (pinfunction "VOS_5") (pintype "passive"))
    )
    (net (code "43") (name "S_+18V") (class "Default")
      (node (ref "R253") (pin "1") (pinfunction "1_1") (pintype "passive"))
    )
  )
)
